# WiFi.net
KiCad netlist of a schematic drawn in Altium Designer
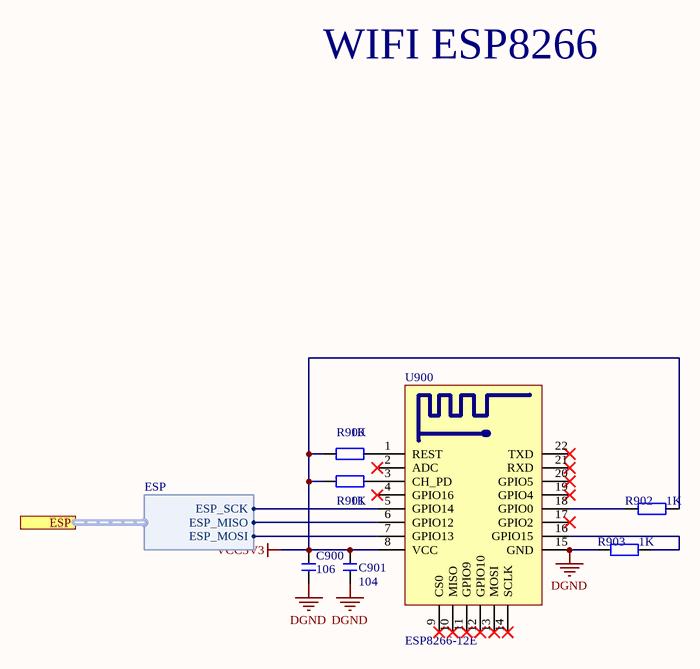
[diagram p0: WiFi.SchDoc]

(export (version "E")
  (design (tool "Eeschema 10.0.6"))
  (components
    (comp (ref "C900")
      (value "106")
      (footprint "C 0402_M")
      (description "无极性贴片电容")
      (fields (field (name "版权归属") "源创客"))
      (libsource (lib "3.1   - 电阻-电容-电感") (part "C"))
    )
    (comp (ref "C901")
      (value "104")
      (footprint "C 0402_M")
      (description "无极性贴片电容")
      (fields (field (name "版权归属") "源创客"))
      (libsource (lib "3.1   - 电阻-电容-电感") (part "C"))
    )
    (comp (ref "R900")
      (value "1K")
      (footprint "R 0402_M")
      (description "贴片电阻")
      (fields (field (name "版权归属") "源创客"))
      (libsource (lib "3.1   - 电阻-电容-电感") (part "R"))
    )
    (comp (ref "R901")
      (value "1K")
      (footprint "R 0402_M")
      (description "贴片电阻")
      (fields (field (name "版权归属") "源创客"))
      (libsource (lib "3.1   - 电阻-电容-电感") (part "R"))
    )
    (comp (ref "R902")
      (value "1K")
      (footprint "R 0402_M")
      (description "贴片电阻")
      (fields (field (name "版权归属") "源创客"))
      (libsource (lib "3.1   - 电阻-电容-电感") (part "R"))
    )
    (comp (ref "R903")
      (value "1K")
      (footprint "R 0402_M")
      (description "贴片电阻")
      (fields (field (name "版权归属") "源创客"))
      (libsource (lib "3.1   - 电阻-电容-电感") (part "R"))
    )
    (comp (ref "U900")
      (value "ESP8266-12E")
      (footprint "ESP_12E")
      (description "串口 WIFI模块，ESP-12E")
      (fields (field (name "版权归属") "源创客"))
      (libsource (lib "13.1 - 模块") (part "ESP8266-12E"))
    )
  )
  (nets
    (net (code "2") (name "/ESP_MISO") (class "Default")
      (node (ref "U900") (pin "6") (pinfunction "GPIO12_6") (pintype "passive"))
    )
    (net (code "3") (name "/ESP_MOSI") (class "Default")
      (node (ref "U900") (pin "7") (pinfunction "GPIO13_7") (pintype "passive"))
    )
    (net (code "4") (name "/ESP_SCK") (class "Default")
      (node (ref "U900") (pin "5") (pinfunction "GPIO14_5") (pintype "passive"))
    )
    (net (code "6") (name "DGND") (class "Default")
      (node (ref "C900") (pin "1") (pinfunction "1_1") (pintype "passive"))
      (node (ref "C901") (pin "1") (pinfunction "1_1") (pintype "passive"))
      (node (ref "R903") (pin "1") (pinfunction "1_1") (pintype "passive"))
      (node (ref "U900") (pin "15") (pinfunction "GND_15") (pintype "passive"))
    )
    (net (code "7") (name "Net-(U900-CH_PD)") (class "Default")
      (node (ref "R901") (pin "2") (pinfunction "2_2") (pintype "passive"))
      (node (ref "U900") (pin "3") (pinfunction "CH_PD_3") (pintype "passive"))
    )
    (net (code "8") (name "Net-(U900-GPIO0)") (class "Default")
      (node (ref "R902") (pin "1") (pinfunction "1_1") (pintype "passive"))
      (node (ref "U900") (pin "18") (pinfunction "GPIO0_18") (pintype "passive"))
    )
    (net (code "9") (name "Net-(U900-GPIO15)") (class "Default")
      (node (ref "R903") (pin "2") (pinfunction "2_2") (pintype "passive"))
      (node (ref "U900") (pin "16") (pinfunction "GPIO15_16") (pintype "passive"))
    )
    (net (code "10") (name "Net-(U900-REST)") (class "Default")
      (node (ref "R900") (pin "2") (pinfunction "2_2") (pintype "passive"))
      (node (ref "U900") (pin "1") (pinfunction "REST_1") (pintype "passive"))
    )
    (net (code "11") (name "VCC3V3") (class "Default")
      (node (ref "C900") (pin "2") (pinfunction "2_2") (pintype "passive"))
      (node (ref "C901") (pin "2") (pinfunction "2_2") (pintype "passive"))
      (node (ref "R900") (pin "1") (pinfunction "1_1") (pintype "passive"))
      (node (ref "R901") (pin "1") (pinfunction "1_1") (pintype "passive"))
      (node (ref "R902") (pin "2") (pinfunction "2_2") (pintype "passive"))
      (node (ref "U900") (pin "8") (pinfunction "VCC_8") (pintype "passive"))
    )
    (net (code "12") (name "unconnected-(U900-ADC-Pad2)") (class "Default")
      (node (ref "U900") (pin "2") (pinfunction "ADC_2") (pintype "passive+no_connect"))
    )
    (net (code "13") (name "unconnected-(U900-CS0-Pad9)") (class "Default")
      (node (ref "U900") (pin "9") (pinfunction "CS0_9") (pintype "passive+no_connect"))
    )
    (net (code "14") (name "unconnected-(U900-GPIO2-Pad17)") (class "Default")
      (node (ref "U900") (pin "17") (pinfunction "GPIO2_17") (pintype "passive+no_connect"))
    )
    (net (code "15") (name "unconnected-(U900-GPIO4-Pad19)") (class "Default")
      (node (ref "U900") (pin "19") (pinfunction "GPIO4_19") (pintype "passive+no_connect"))
    )
    (net (code "16") (name "unconnected-(U900-GPIO5-Pad20)") (class "Default")
      (node (ref "U900") (pin "20") (pinfunction "GPIO5_20") (pintype "passive+no_connect"))
    )
    (net (code "17") (name "unconnected-(U900-GPIO9-Pad11)") (class "Default")
      (node (ref "U900") (pin "11") (pinfunction "GPIO9_11") (pintype "passive+no_connect"))
    )
    (net (code "18") (name "unconnected-(U900-GPIO10-Pad12)") (class "Default")
      (node (ref "U900") (pin "12") (pinfunction "GPIO10_12") (pintype "passive+no_connect"))
    )
    (net (code "19") (name "unconnected-(U900-GPIO16-Pad4)") (class "Default")
      (node (ref "U900") (pin "4") (pinfunction "GPIO16_4") (pintype "passive+no_connect"))
    )
    (net (code "20") (name "unconnected-(U900-MISO-Pad10)") (class "Default")
      (node (ref "U900") (pin "10") (pinfunction "MISO_10") (pintype "passive+no_connect"))
    )
    (net (code "21") (name "unconnected-(U900-MOSI-Pad13)") (class "Default")
      (node (ref "U900") (pin "13") (pinfunction "MOSI_13") (pintype "passive+no_connect"))
    )
    (net (code "22") (name "unconnected-(U900-RXD-Pad21)") (class "Default")
      (node (ref "U900") (pin "21") (pinfunction "RXD_21") (pintype "passive+no_connect"))
    )
    (net (code "23") (name "unconnected-(U900-SCLK-Pad14)") (class "Default")
      (node (ref "U900") (pin "14") (pinfunction "SCLK_14") (pintype "passive+no_connect"))
    )
    (net (code "24") (name "unconnected-(U900-TXD-Pad22)") (class "Default")
      (node (ref "U900") (pin "22") (pinfunction "TXD_22") (pintype "passive+no_connect"))
    )
  )
)
